# m66.net
KiCad netlist of a schematic drawn in Altium Designer
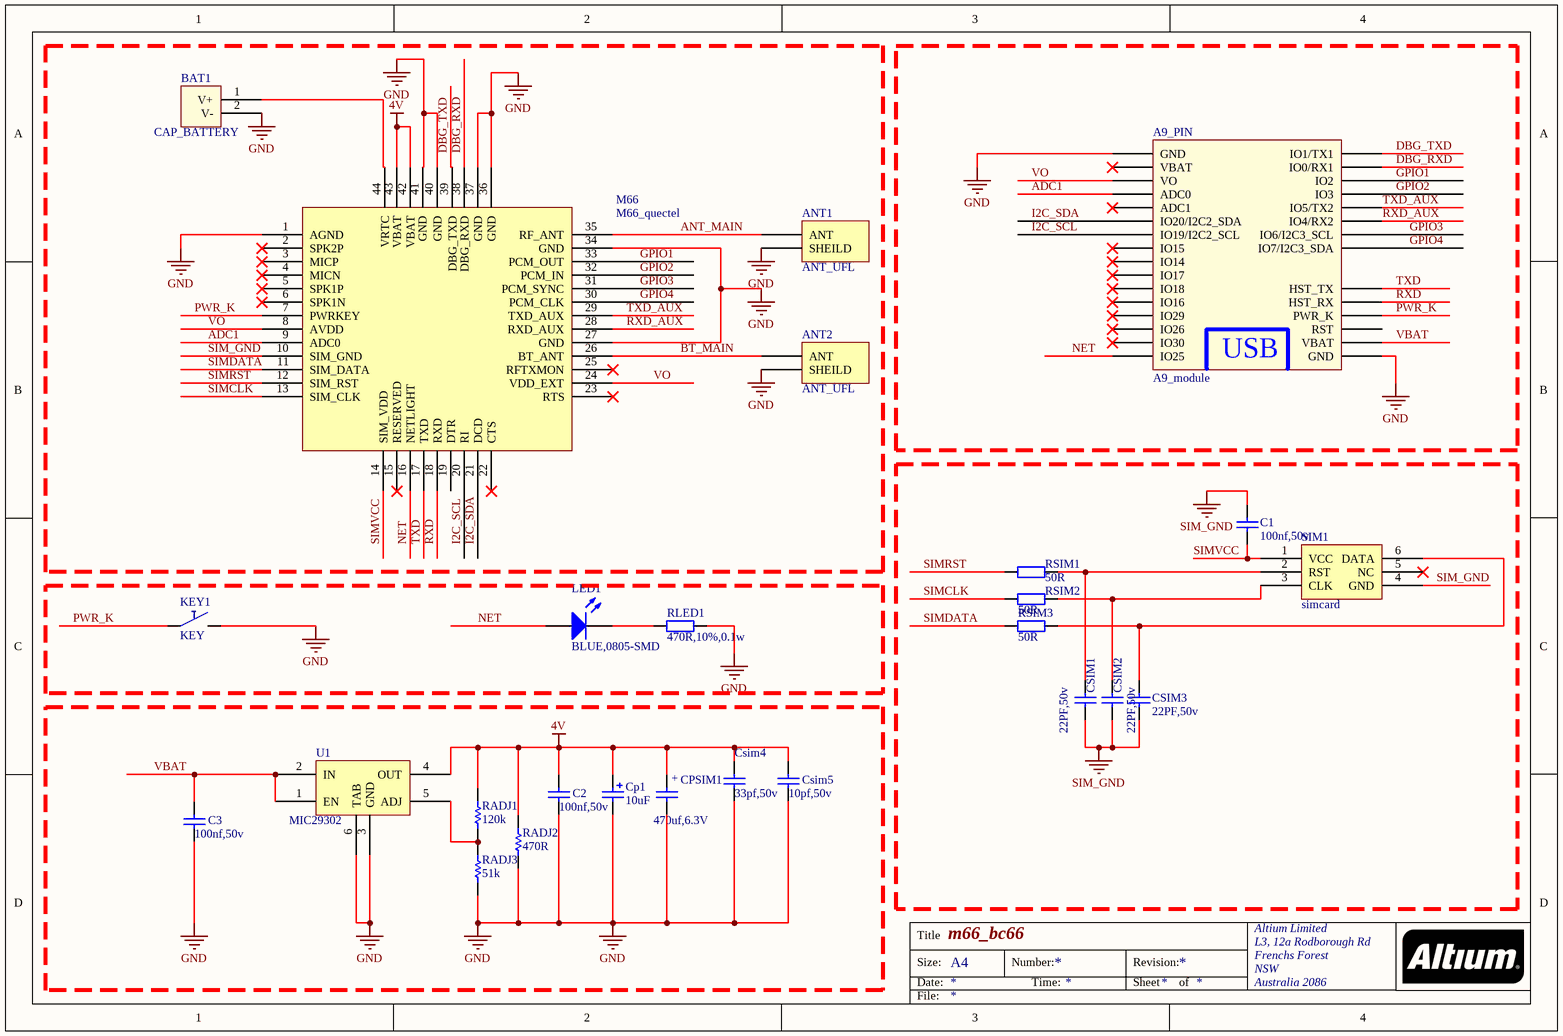
[diagram p0: m66.SchDoc]

(export (version "E")
  (design (tool "Eeschema 10.0.6"))
  (components
    (comp (ref "A9_PIN")
      (value "A9_module")
      (footprint "A9_MODULE")
      (libsource (lib "armlib") (part "A9_module"))
    )
    (comp (ref "ANT1") (value "ANT_UFL") (footprint "UFL_CON") (libsource (lib "armlib") (part "ANT_UFL")))
    (comp (ref "ANT2") (value "ANT_UFL") (footprint "UFL_CON") (libsource (lib "armlib") (part "ANT_UFL")))
    (comp (ref "BAT1")
      (value "CAP_BATTERY")
      (footprint "CAP_BAT")
      (libsource (lib "armlib") (part "CAP_BATTERY"))
    )
    (comp (ref "C1")
      (value "100nf,50v")
      (footprint "0805.")
      (description "Capacitor")
      (fields (field (name "PUBLISHER") "Altium Limited"))
      (libsource (lib "STM32F407VG") (part "Cap"))
    )
    (comp (ref "C2")
      (value "100nf,50v")
      (footprint "0805.")
      (description "Capacitor")
      (fields (field (name "PUBLISHER") "Altium Limited"))
      (libsource (lib "MBIO-SCHPCB-MBFD-REV1") (part "Cap"))
    )
    (comp (ref "C3")
      (value "100nf,50v")
      (footprint "0805.")
      (description "Capacitor")
      (fields (field (name "PUBLISHER") "Altium Limited"))
      (libsource (lib "MBIO-SCHPCB-MBFD-REV1") (part "Cap"))
    )
    (comp (ref "Cp1")
      (value "10uF")
      (footprint "C1206.")
      (description "Polarized Capacitor (Radial)")
      (fields (field (name "PUBLISHER") "Altium Limited"))
      (libsource (lib "PCB_Project1") (part "Cap Pol1"))
    )
    (comp (ref "CPSIM1")
      (value "470uf,6.3V")
      (footprint "MY_SMC_D")
      (description "Polar capacitor")
      (fields (field (name "ASID PART NUMBER") "C-AS"))
      (libsource (lib "TPS54331") (part "Cap Pol"))
    )
    (comp (ref "CSIM1")
      (value "22PF,50v")
      (footprint "0805.")
      (description "Capacitor")
      (fields (field (name "PUBLISHER") "Altium Limited"))
      (libsource (lib "MBIO-SCHPCB-MBFD-REV1") (part "Cap"))
    )
    (comp (ref "CSIM2")
      (value "22PF,50v")
      (footprint "0805.")
      (description "Capacitor")
      (fields (field (name "PUBLISHER") "Altium Limited"))
      (libsource (lib "MBIO-SCHPCB-MBFD-REV1") (part "Cap"))
    )
    (comp (ref "CSIM3")
      (value "22PF,50v")
      (footprint "0805.")
      (description "Capacitor")
      (fields (field (name "PUBLISHER") "Altium Limited"))
      (libsource (lib "MBIO-SCHPCB-MBFD-REV1") (part "Cap"))
    )
    (comp (ref "Csim4")
      (value "33pf,50v")
      (footprint "0805.")
      (description "Capacitor")
      (fields (field (name "PUBLISHER") "Altium Limited"))
      (libsource (lib "MBIO-SCHPCB-MBFD-REV1") (part "Cap"))
    )
    (comp (ref "Csim5")
      (value "10pf,50v")
      (footprint "0805.")
      (description "Capacitor")
      (fields (field (name "PUBLISHER") "Altium Limited"))
      (libsource (lib "MBIO-SCHPCB-MBFD-REV1") (part "Cap"))
    )
    (comp (ref "KEY1") (value "KEY") (footprint "SMD_KEY") (libsource (lib "armlib") (part "KEY")))
    (comp (ref "LED1")
      (value "BLUE,0805-SMD")
      (footprint "0805.")
      (description "Typical INFRARED GaAs LED")
      (fields (field (name "PUBLISHER") "Altium Limited"))
      (libsource (lib "MBIO-SCHPCB-MBFD-REV1") (part "LED0"))
    )
    (comp (ref "M66")
      (value "M66_quectel")
      (footprint "M66_QUECTEL")
      (libsource (lib "armlib") (part "M66_quectel"))
    )
    (comp (ref "RADJ1")
      (value "120k")
      (footprint "0805.")
      (description "Resistor")
      (fields (field (name "PUBLISHER") "Altium Limited"))
      (libsource (lib "PCB_Project1") (part "Res1"))
    )
    (comp (ref "RADJ2")
      (value "470R")
      (footprint "0805.")
      (description "Resistor")
      (fields (field (name "PUBLISHER") "Altium Limited"))
      (libsource (lib "PCB_Project1") (part "Res1"))
    )
    (comp (ref "RADJ3")
      (value "51k")
      (footprint "0805.")
      (description "Resistor")
      (fields (field (name "PUBLISHER") "Altium Limited"))
      (libsource (lib "PCB_Project1") (part "Res1"))
    )
    (comp (ref "RLED1")
      (value "470R,10%,0.1w")
      (footprint "0805.")
      (description "Resistor")
      (fields (field (name "PUBLISHER") "Altium Limited"))
      (libsource (lib "MBIO-SCHPCB-MBFD-REV1") (part "Res2"))
    )
    (comp (ref "RSIM1")
      (value "50R")
      (footprint "0805.")
      (description "Resistor")
      (fields (field (name "Comment") "47R,10%,0.1w") (field (name "PUBLISHER") "Altium Limited"))
      (libsource (lib "PCB_Project1") (part "Res2"))
    )
    (comp (ref "RSIM2")
      (value "50R")
      (footprint "0805.")
      (description "Resistor")
      (fields (field (name "Comment") "47R,10%,0.1w") (field (name "PUBLISHER") "Altium Limited"))
      (libsource (lib "PCB_Project1") (part "Res2"))
    )
    (comp (ref "RSIM3")
      (value "50R")
      (footprint "0805.")
      (description "Resistor")
      (fields (field (name "Comment") "47R,10%,0.1w") (field (name "PUBLISHER") "Altium Limited"))
      (libsource (lib "PCB_Project1") (part "Res2"))
    )
    (comp (ref "SIM1") (value "simcard") (footprint "SIMCARD_M") (libsource (lib "armlib") (part "simcard")))
    (comp (ref "U1") (value "MIC29302") (footprint "MIC29302") (libsource (lib "armlib") (part "MIC29302")))
  )
  (nets
    (net (code "1") (name "/ADC1") (class "Default")
      (node (ref "A9_PIN") (pin "4") (pinfunction "ADC0_4") (pintype "passive"))
      (node (ref "M66") (pin "9") (pinfunction "ADC0_9") (pintype "passive"))
    )
    (net (code "2") (name "/ANT_MAIN") (class "Default")
      (node (ref "ANT1") (pin "2") (pinfunction "ANT_2") (pintype "passive"))
      (node (ref "M66") (pin "35") (pinfunction "RF_ANT_35") (pintype "passive"))
    )
    (net (code "3") (name "/BT_MAIN") (class "Default")
      (node (ref "ANT2") (pin "2") (pinfunction "ANT_2") (pintype "passive"))
      (node (ref "M66") (pin "26") (pinfunction "BT_ANT_26") (pintype "passive"))
    )
    (net (code "4") (name "/DBG_RXD") (class "Default")
      (node (ref "A9_PIN") (pin "29") (pinfunction "IO0/RX1_29") (pintype "passive"))
      (node (ref "M66") (pin "38") (pinfunction "DBG_RXD_38") (pintype "passive"))
    )
    (net (code "5") (name "/DBG_TXD") (class "Default")
      (node (ref "A9_PIN") (pin "30") (pinfunction "IO1/TX1_30") (pintype "passive"))
      (node (ref "M66") (pin "39") (pinfunction "DBG_TXD_39") (pintype "passive"))
    )
    (net (code "6") (name "/GPIO1") (class "Default")
      (node (ref "A9_PIN") (pin "28") (pinfunction "IO2_28") (pintype "passive"))
      (node (ref "M66") (pin "33") (pinfunction "PCM_OUT_33") (pintype "passive"))
    )
    (net (code "7") (name "/GPIO2") (class "Default")
      (node (ref "A9_PIN") (pin "27") (pinfunction "IO3_27") (pintype "passive"))
      (node (ref "M66") (pin "32") (pinfunction "PCM_IN_32") (pintype "passive"))
    )
    (net (code "8") (name "/GPIO3") (class "Default")
      (node (ref "A9_PIN") (pin "24") (pinfunction "IO6/I2C3_SCL_24") (pintype "passive"))
      (node (ref "M66") (pin "31") (pinfunction "PCM_SYNC_31") (pintype "passive"))
    )
    (net (code "9") (name "/GPIO4") (class "Default")
      (node (ref "A9_PIN") (pin "23") (pinfunction "IO7/I2C3_SDA_23") (pintype "passive"))
      (node (ref "M66") (pin "30") (pinfunction "PCM_CLK_30") (pintype "passive"))
    )
    (net (code "10") (name "/I2C_SCL") (class "Default")
      (node (ref "A9_PIN") (pin "7") (pinfunction "IO19/I2C2_SCL_7") (pintype "passive"))
      (node (ref "M66") (pin "20") (pinfunction "RI_20") (pintype "passive"))
    )
    (net (code "11") (name "/I2C_SDA") (class "Default")
      (node (ref "A9_PIN") (pin "6") (pinfunction "IO20/I2C2_SDA_6") (pintype "passive"))
      (node (ref "M66") (pin "21") (pinfunction "DCD_21") (pintype "passive"))
    )
    (net (code "12") (name "/NET") (class "Default")
      (node (ref "A9_PIN") (pin "16") (pinfunction "IO25_16") (pintype "passive"))
      (node (ref "LED1") (pin "2") (pinfunction "A_2") (pintype "passive"))
      (node (ref "M66") (pin "16") (pinfunction "NETLIGHT_16") (pintype "passive"))
    )
    (net (code "13") (name "/PWR_K") (class "Default")
      (node (ref "A9_PIN") (pin "20") (pinfunction "PWR_K_20") (pintype "passive"))
      (node (ref "KEY1") (pin "1") (pinfunction "1_1") (pintype "passive"))
      (node (ref "M66") (pin "7") (pinfunction "PWRKEY_7") (pintype "passive"))
    )
    (net (code "14") (name "/RXD") (class "Default")
      (node (ref "A9_PIN") (pin "21") (pinfunction "HST_RX_21") (pintype "passive"))
      (node (ref "M66") (pin "18") (pinfunction "RXD_18") (pintype "passive"))
    )
    (net (code "15") (name "/RXD_AUX") (class "Default")
      (node (ref "A9_PIN") (pin "25") (pinfunction "IO4/RX2_25") (pintype "passive"))
      (node (ref "M66") (pin "28") (pinfunction "RXD_AUX_28") (pintype "passive"))
    )
    (net (code "16") (name "/SIMCLK") (class "Default")
      (node (ref "M66") (pin "13") (pinfunction "SIM_CLK_13") (pintype "passive"))
      (node (ref "RSIM2") (pin "1") (pinfunction "1_1") (pintype "passive"))
    )
    (net (code "17") (name "/SIMDATA") (class "Default")
      (node (ref "M66") (pin "11") (pinfunction "SIM_DATA_11") (pintype "passive"))
      (node (ref "RSIM3") (pin "1") (pinfunction "1_1") (pintype "passive"))
    )
    (net (code "18") (name "/SIMRST") (class "Default")
      (node (ref "M66") (pin "12") (pinfunction "SIM_RST_12") (pintype "passive"))
      (node (ref "RSIM1") (pin "1") (pinfunction "1_1") (pintype "passive"))
    )
    (net (code "19") (name "/SIMVCC") (class "Default")
      (node (ref "C1") (pin "1") (pinfunction "1_1") (pintype "passive"))
      (node (ref "M66") (pin "14") (pinfunction "SIM_VDD_14") (pintype "passive"))
      (node (ref "SIM1") (pin "1") (pinfunction "VCC_1") (pintype "passive"))
    )
    (net (code "20") (name "/TXD") (class "Default")
      (node (ref "A9_PIN") (pin "22") (pinfunction "HST_TX_22") (pintype "passive"))
      (node (ref "M66") (pin "17") (pinfunction "TXD_17") (pintype "passive"))
    )
    (net (code "21") (name "/TXD_AUX") (class "Default")
      (node (ref "A9_PIN") (pin "26") (pinfunction "IO5/TX2_26") (pintype "passive"))
      (node (ref "M66") (pin "29") (pinfunction "TXD_AUX_29") (pintype "passive"))
    )
    (net (code "22") (name "/VBAT") (class "Default")
      (node (ref "A9_PIN") (pin "18") (pinfunction "VBAT_18") (pintype "passive"))
      (node (ref "C3") (pin "2") (pinfunction "2_2") (pintype "passive"))
      (node (ref "U1") (pin "1") (pinfunction "EN_1") (pintype "passive"))
      (node (ref "U1") (pin "2") (pinfunction "IN_2") (pintype "passive"))
    )
    (net (code "23") (name "/VO") (class "Default")
      (node (ref "A9_PIN") (pin "3") (pinfunction "VO_3") (pintype "passive"))
      (node (ref "M66") (pin "24") (pinfunction "VDD_EXT_24") (pintype "passive"))
      (node (ref "M66") (pin "8") (pinfunction "AVDD_8") (pintype "passive"))
    )
    (net (code "24") (name "4V") (class "Default")
      (node (ref "C2") (pin "2") (pinfunction "2_2") (pintype "passive"))
      (node (ref "CPSIM1") (pin "+") (pinfunction "+_+") (pintype "passive"))
      (node (ref "Cp1") (pin "1") (pinfunction "1_1") (pintype "passive"))
      (node (ref "Csim4") (pin "2") (pinfunction "2_2") (pintype "passive"))
      (node (ref "Csim5") (pin "2") (pinfunction "2_2") (pintype "passive"))
      (node (ref "M66") (pin "42") (pinfunction "VBAT_42") (pintype "passive"))
      (node (ref "M66") (pin "43") (pinfunction "VBAT_43") (pintype "passive"))
      (node (ref "RADJ1") (pin "2") (pinfunction "2_2") (pintype "passive"))
      (node (ref "RADJ2") (pin "2") (pinfunction "2_2") (pintype "passive"))
      (node (ref "U1") (pin "4") (pinfunction "OUT_4") (pintype "passive"))
    )
    (net (code "25") (name "GND") (class "Default")
      (node (ref "A9_PIN") (pin "1") (pinfunction "GND_1") (pintype "passive"))
      (node (ref "A9_PIN") (pin "17") (pinfunction "GND_17") (pintype "passive"))
      (node (ref "ANT1") (pin "1") (pinfunction "SHEILD_1") (pintype "passive"))
      (node (ref "ANT2") (pin "1") (pinfunction "SHEILD_1") (pintype "passive"))
      (node (ref "BAT1") (pin "2") (pinfunction "V-_2") (pintype "passive"))
      (node (ref "C2") (pin "1") (pinfunction "1_1") (pintype "passive"))
      (node (ref "C3") (pin "1") (pinfunction "1_1") (pintype "passive"))
      (node (ref "CPSIM1") (pin "-") (pinfunction "-_-") (pintype "passive"))
      (node (ref "Cp1") (pin "2") (pinfunction "2_2") (pintype "passive"))
      (node (ref "Csim4") (pin "1") (pinfunction "1_1") (pintype "passive"))
      (node (ref "Csim5") (pin "1") (pinfunction "1_1") (pintype "passive"))
      (node (ref "KEY1") (pin "2") (pinfunction "2_2") (pintype "passive"))
      (node (ref "M66") (pin "1") (pinfunction "AGND_1") (pintype "passive"))
      (node (ref "M66") (pin "27") (pinfunction "GND_27") (pintype "passive"))
      (node (ref "M66") (pin "34") (pinfunction "GND_34") (pintype "passive"))
      (node (ref "M66") (pin "36") (pinfunction "GND_36") (pintype "passive"))
      (node (ref "M66") (pin "37") (pinfunction "GND_37") (pintype "passive"))
      (node (ref "M66") (pin "40") (pinfunction "GND_40") (pintype "passive"))
      (node (ref "M66") (pin "41") (pinfunction "GND_41") (pintype "passive"))
      (node (ref "RADJ2") (pin "1") (pinfunction "1_1") (pintype "passive"))
      (node (ref "RADJ3") (pin "1") (pinfunction "1_1") (pintype "passive"))
      (node (ref "RLED1") (pin "2") (pinfunction "2_2") (pintype "passive"))
      (node (ref "U1") (pin "3") (pinfunction "GND_3") (pintype "passive"))
      (node (ref "U1") (pin "6") (pinfunction "TAB_6") (pintype "passive"))
    )
    (net (code "26") (name "Net-(BAT1-V+)") (class "Default")
      (node (ref "BAT1") (pin "1") (pinfunction "V+_1") (pintype "passive"))
      (node (ref "M66") (pin "44") (pinfunction "VRTC_44") (pintype "passive"))
    )
    (net (code "27") (name "Net-(LED1-K)") (class "Default")
      (node (ref "LED1") (pin "1") (pinfunction "K_1") (pintype "passive"))
      (node (ref "RLED1") (pin "1") (pinfunction "1_1") (pintype "passive"))
    )
    (net (code "28") (name "Net-(SIM1-CLK)") (class "Default")
      (node (ref "CSIM2") (pin "2") (pinfunction "2_2") (pintype "passive"))
      (node (ref "RSIM2") (pin "2") (pinfunction "2_2") (pintype "passive"))
      (node (ref "SIM1") (pin "3") (pinfunction "CLK_3") (pintype "passive"))
    )
    (net (code "29") (name "Net-(SIM1-DATA)") (class "Default")
      (node (ref "CSIM3") (pin "2") (pinfunction "2_2") (pintype "passive"))
      (node (ref "RSIM3") (pin "2") (pinfunction "2_2") (pintype "passive"))
      (node (ref "SIM1") (pin "6") (pinfunction "DATA_6") (pintype "passive"))
    )
    (net (code "30") (name "Net-(SIM1-RST)") (class "Default")
      (node (ref "CSIM1") (pin "2") (pinfunction "2_2") (pintype "passive"))
      (node (ref "RSIM1") (pin "2") (pinfunction "2_2") (pintype "passive"))
      (node (ref "SIM1") (pin "2") (pinfunction "RST_2") (pintype "passive"))
    )
    (net (code "31") (name "Net-(U1-ADJ)") (class "Default")
      (node (ref "RADJ1") (pin "1") (pinfunction "1_1") (pintype "passive"))
      (node (ref "RADJ3") (pin "2") (pinfunction "2_2") (pintype "passive"))
      (node (ref "U1") (pin "5") (pinfunction "ADJ_5") (pintype "passive"))
    )
    (net (code "32") (name "SIM_GND") (class "Default")
      (node (ref "C1") (pin "2") (pinfunction "2_2") (pintype "passive"))
      (node (ref "CSIM1") (pin "1") (pinfunction "1_1") (pintype "passive"))
      (node (ref "CSIM2") (pin "1") (pinfunction "1_1") (pintype "passive"))
      (node (ref "CSIM3") (pin "1") (pinfunction "1_1") (pintype "passive"))
      (node (ref "M66") (pin "10") (pinfunction "SIM_GND_10") (pintype "passive"))
      (node (ref "SIM1") (pin "4") (pinfunction "GND_4") (pintype "passive"))
    )
    (net (code "33") (name "unconnected-(A9_PIN-ADC1-Pad5)") (class "Default")
      (node (ref "A9_PIN") (pin "5") (pinfunction "ADC1_5") (pintype "passive+no_connect"))
    )
    (net (code "34") (name "unconnected-(A9_PIN-IO14-Pad9)") (class "Default")
      (node (ref "A9_PIN") (pin "9") (pinfunction "IO14_9") (pintype "passive+no_connect"))
    )
    (net (code "35") (name "unconnected-(A9_PIN-IO15-Pad8)") (class "Default")
      (node (ref "A9_PIN") (pin "8") (pinfunction "IO15_8") (pintype "passive+no_connect"))
    )
    (net (code "36") (name "unconnected-(A9_PIN-IO16-Pad12)") (class "Default")
      (node (ref "A9_PIN") (pin "12") (pinfunction "IO16_12") (pintype "passive+no_connect"))
    )
    (net (code "37") (name "unconnected-(A9_PIN-IO17-Pad10)") (class "Default")
      (node (ref "A9_PIN") (pin "10") (pinfunction "IO17_10") (pintype "passive+no_connect"))
    )
    (net (code "38") (name "unconnected-(A9_PIN-IO18-Pad11)") (class "Default")
      (node (ref "A9_PIN") (pin "11") (pinfunction "IO18_11") (pintype "passive+no_connect"))
    )
    (net (code "39") (name "unconnected-(A9_PIN-IO26-Pad14)") (class "Default")
      (node (ref "A9_PIN") (pin "14") (pinfunction "IO26_14") (pintype "passive+no_connect"))
    )
    (net (code "40") (name "unconnected-(A9_PIN-IO29-Pad13)") (class "Default")
      (node (ref "A9_PIN") (pin "13") (pinfunction "IO29_13") (pintype "passive+no_connect"))
    )
    (net (code "41") (name "unconnected-(A9_PIN-IO30-Pad15)") (class "Default")
      (node (ref "A9_PIN") (pin "15") (pinfunction "IO30_15") (pintype "passive+no_connect"))
    )
    (net (code "42") (name "unconnected-(A9_PIN-RST-Pad19)") (class "Default")
      (node (ref "A9_PIN") (pin "19") (pinfunction "RST_19") (pintype "passive"))
    )
    (net (code "43") (name "unconnected-(A9_PIN-VBAT-Pad2)") (class "Default")
      (node (ref "A9_PIN") (pin "2") (pinfunction "VBAT_2") (pintype "passive+no_connect"))
    )
    (net (code "44") (name "unconnected-(M66-CTS-Pad22)") (class "Default")
      (node (ref "M66") (pin "22") (pinfunction "CTS_22") (pintype "passive+no_connect"))
    )
    (net (code "45") (name "unconnected-(M66-DTR-Pad19)") (class "Default")
      (node (ref "M66") (pin "19") (pinfunction "DTR_19") (pintype "passive"))
    )
    (net (code "46") (name "unconnected-(M66-MICN-Pad4)") (class "Default")
      (node (ref "M66") (pin "4") (pinfunction "MICN_4") (pintype "passive+no_connect"))
    )
    (net (code "47") (name "unconnected-(M66-MICP-Pad3)") (class "Default")
      (node (ref "M66") (pin "3") (pinfunction "MICP_3") (pintype "passive+no_connect"))
    )
    (net (code "48") (name "unconnected-(M66-RESERVED-Pad15)") (class "Default")
      (node (ref "M66") (pin "15") (pinfunction "RESERVED_15") (pintype "passive+no_connect"))
    )
    (net (code "49") (name "unconnected-(M66-RFTXMON-Pad25)") (class "Default")
      (node (ref "M66") (pin "25") (pinfunction "RFTXMON_25") (pintype "passive+no_connect"))
    )
    (net (code "50") (name "unconnected-(M66-RTS-Pad23)") (class "Default")
      (node (ref "M66") (pin "23") (pinfunction "RTS_23") (pintype "passive+no_connect"))
    )
    (net (code "51") (name "unconnected-(M66-SPK1N-Pad6)") (class "Default")
      (node (ref "M66") (pin "6") (pinfunction "SPK1N_6") (pintype "passive+no_connect"))
    )
    (net (code "52") (name "unconnected-(M66-SPK1P-Pad5)") (class "Default")
      (node (ref "M66") (pin "5") (pinfunction "SPK1P_5") (pintype "passive+no_connect"))
    )
    (net (code "53") (name "unconnected-(M66-SPK2P-Pad2)") (class "Default")
      (node (ref "M66") (pin "2") (pinfunction "SPK2P_2") (pintype "passive+no_connect"))
    )
    (net (code "54") (name "unconnected-(SIM1-NC-Pad5)") (class "Default")
      (node (ref "SIM1") (pin "5") (pinfunction "NC_5") (pintype "passive+no_connect"))
    )
  )
)
